# lorabreakout.net
KiCad netlist of a schematic drawn in Altium Designer
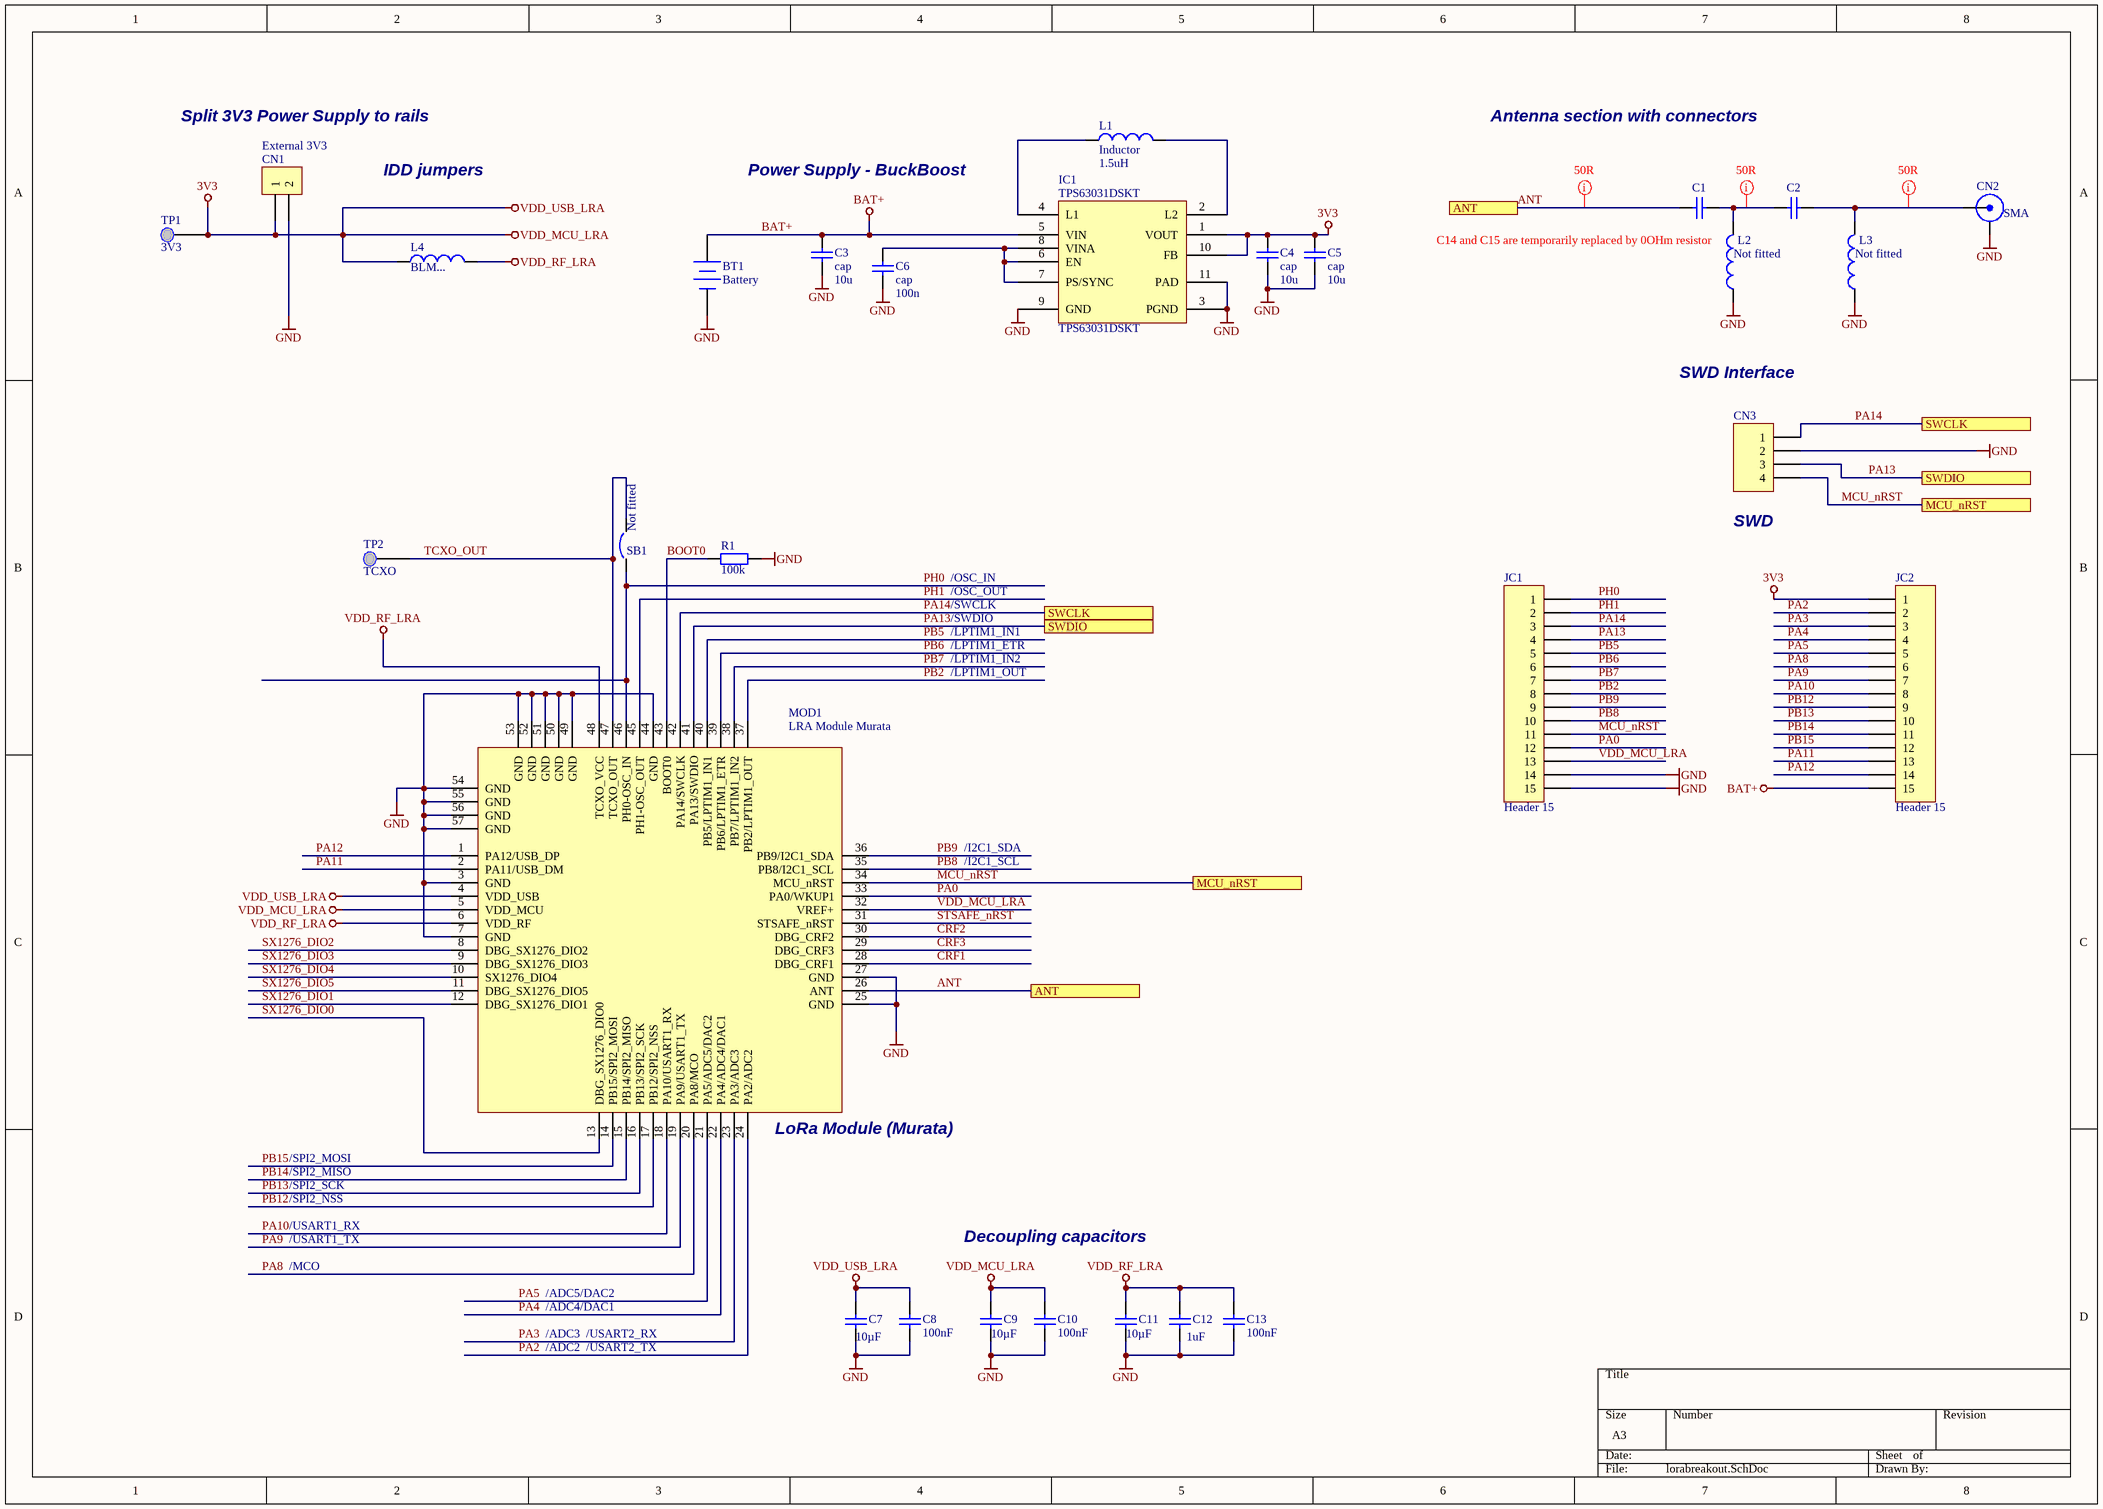
[diagram p0: lorabreakout.SchDoc]

(export (version "E")
  (design (tool "Eeschema 10.0.6"))
  (components
    (comp (ref "BT1")
      (value "Battery")
      (footprint "SIP2")
      (description "Multicell Battery")
      (fields (field (name "PUBLISHER") "Altium Limited"))
      (libsource (lib "Miscellaneous Devices") (part "Battery"))
    )
    (comp (ref "C1")
      (value "~")
      (footprint "0402")
      (description "0402")
      (libsource (lib "Capacitor_0402") (part "CAP SMD 0402 NPO 18PF 16V 5%"))
    )
    (comp (ref "C2")
      (value "~")
      (footprint "0402")
      (description "0402")
      (libsource (lib "Capacitor_0402") (part "CAP SMD 0402 NPO 18PF 16V 5%"))
    )
    (comp (ref "C3")
      (value "cap")
      (footprint "0603ok")
      (description "Capacitor")
      (fields (field (name "ALTIUM_VALUE") "10u") (field (name "PUBLISHER") "Altium Limited"))
      (libsource (lib "Miscellaneous Devices") (part "Cap"))
    )
    (comp (ref "C4")
      (value "cap")
      (footprint "0603ok")
      (description "Capacitor")
      (fields (field (name "ALTIUM_VALUE") "10u") (field (name "PUBLISHER") "Altium Limited"))
      (libsource (lib "Miscellaneous Devices") (part "Cap"))
    )
    (comp (ref "C5")
      (value "cap")
      (footprint "0603ok")
      (description "Capacitor")
      (fields (field (name "ALTIUM_VALUE") "10u") (field (name "PUBLISHER") "Altium Limited"))
      (libsource (lib "Miscellaneous Devices") (part "Cap"))
    )
    (comp (ref "C6")
      (value "cap")
      (footprint "0603ok")
      (description "Capacitor")
      (fields (field (name "ALTIUM_VALUE") "100n") (field (name "PUBLISHER") "Altium Limited"))
      (libsource (lib "Miscellaneous Devices") (part "Cap"))
    )
    (comp (ref "C7")
      (value "10µF")
      (footprint "0603C")
      (description "Capacitor SMD 0805 10000000pF X7R 10V +/-10%")
      (fields (field (name "MANUFACTURER") "Kemet") (field (name "TOLERANCE") "10%"))
      (libsource (lib "Capacitor_0805") (part "CAP_C0805C106K8RACTU"))
    )
    (comp (ref "C8")
      (value "100nF")
      (footprint "0603C")
      (description "Capacitor 100nF")
      (fields (field (name "MANUFACTURER") "YAGEO") (field (name "PROVIDED BY") "Subcon"))
      (libsource (lib "MCD16-033-STM32_LRA_Eval_Board_1") (part "CAP"))
    )
    (comp (ref "C9")
      (value "10µF")
      (footprint "0603C")
      (description "Capacitor SMD 0805 10000000pF X7R 10V +/-10%")
      (fields (field (name "MANUFACTURER") "Kemet") (field (name "TOLERANCE") "10%"))
      (libsource (lib "Capacitor_0805") (part "CAP_C0805C106K8RACTU"))
    )
    (comp (ref "C10")
      (value "100nF")
      (footprint "0603C")
      (description "Capacitor 100nF")
      (fields (field (name "MANUFACTURER") "YAGEO") (field (name "PROVIDED BY") "Subcon"))
      (libsource (lib "MCD16-033-STM32_LRA_Eval_Board_1") (part "CAP"))
    )
    (comp (ref "C11")
      (value "10µF")
      (footprint "0603C")
      (description "Capacitor SMD 0805 10000000pF X7R 10V +/-10%")
      (fields (field (name "MANUFACTURER") "Kemet") (field (name "TOLERANCE") "10%"))
      (libsource (lib "Capacitor_0805") (part "CAP_C0805C106K8RACTU"))
    )
    (comp (ref "C12")
      (value "1uF")
      (footprint "0603C")
      (description "0603  X5R 1µF")
      (fields (field (name "MANUFACTURER") "YAGEO") (field (name "PROVIDED BY") "Subcon"))
      (libsource (lib "MCD16-033-STM32_LRA_Eval_Board_1") (part "CAP SMD 0603  X5R 1µF 25V 10%"))
    )
    (comp (ref "C13")
      (value "100nF")
      (footprint "0603C")
      (description "Capacitor 100nF")
      (fields (field (name "MANUFACTURER") "YAGEO") (field (name "PROVIDED BY") "Subcon"))
      (libsource (lib "MCD16-033-STM32_LRA_Eval_Board_1") (part "CAP"))
    )
    (comp (ref "CN1")
      (value "External 3V3")
      (footprint "SIP2")
      (description "Header 2")
      (fields (field (name "MANUFACTURER") "Kontek") (field (name "PROVIDED BY") "Subcon"))
      (libsource (lib "MCD16-033-STM32_LRA_Eval_Board_1") (part "Header 2"))
    )
    (comp (ref "CN2")
      (value "SMA")
      (footprint "SMA_COMBO_B")
      (libsource (lib "SCH_Lib_Phil_ST") (part "SMA"))
    )
    (comp (ref "CN3")
      (value "Header 4")
      (footprint "SIP4")
      (description "Header, 4-Pin, Single row")
      (fields (field (name "MANUFACTURER") "Lyconn") (field (name "PROVIDED BY") "Subcon"))
      (libsource (lib "MCD16-033-STM32_LRA_Eval_Board_1") (part "Header 4"))
    )
    (comp (ref "IC1")
      (value "TPS63031DSKT")
      (footprint "QFN50P250X250X80_HS-11N")
      (libsource (lib "moja") (part "TPS63031DSKT"))
    )
    (comp (ref "JC1")
      (value "Header 15")
      (footprint "HDR1X15")
      (description "Header, 15-Pin")
      (fields (field (name "PUBLISHER") "Altium Limited"))
      (libsource (lib "") (part "Header 15_1"))
    )
    (comp (ref "JC2")
      (value "Header 15")
      (footprint "HDR1X15")
      (description "Header, 15-Pin")
      (fields (field (name "PUBLISHER") "Altium Limited"))
      (libsource (lib "Miscellaneous Connectors") (part "Header 15"))
    )
    (comp (ref "L1")
      (value "Inductor")
      (footprint "lps3015")
      (fields (field (name "ALTIUM_VALUE") "1.5uH") (field (name "PUBLISHER") "Altium Limited"))
      (libsource (lib "Miscellaneous Devices") (part "Inductor"))
    )
    (comp (ref "L2")
      (value "~")
      (footprint "0402")
      (libsource (lib "MCD16-033-STM32_LRA_Eval_Board_1") (part "BLM15HG102SN1D"))
    )
    (comp (ref "L3")
      (value "~")
      (footprint "0402")
      (libsource (lib "MCD16-033-STM32_LRA_Eval_Board_1") (part "BLM15HG102SN1D"))
    )
    (comp (ref "L4")
      (value "BLM...")
      (footprint "0603ok")
      (description "BLM15HG102SN1D")
      (fields (field (name "MANUFACTURER") "Murata Electronics"))
      (libsource (lib "MCD16-033-STM32_LRA_Eval_Board_1") (part "BLM15HG102SN1D"))
    )
    (comp (ref "MOD1")
      (value "LRA Module Murata")
      (footprint "Lora Module ES0")
      (description "LRA Module ES0")
      (fields (field (name "MANUFACTURER") "Murata") (field (name "PROVIDED BY") "Murata"))
      (libsource (lib "Integrated_Circuit") (part "LRA Module ES0"))
    )
    (comp (ref "R1")
      (value "100k")
      (footprint "0402")
      (description "2k2")
      (fields (field (name "Comment") "Res2") (field (name "PUBLISHER") "Altium Limited"))
      (libsource (lib "Miscellaneous Devices") (part "Res2"))
    )
    (comp (ref "SB1")
      (value "Circuit Breaker")
      (footprint "JP2_SMD")
      (libsource (lib "MCD16-033-STM32_LRA_Eval_Board_1") (part "Circuit Breaker"))
    )
    (comp (ref "TP1") (value "3V3") (footprint "SMD-MINITP") (libsource (lib "moja") (part "Testpoint")))
    (comp (ref "TP2") (value "TCXO") (footprint "SMD-MINITP") (libsource (lib "moja") (part "Testpoint")))
  )
  (nets
    (net (code "1") (name "/ANT") (class "Default")
      (node (ref "C1") (pin "1") (pinfunction "1_1") (pintype "passive"))
      (node (ref "MOD1") (pin "26") (pinfunction "ANT_26") (pintype "passive"))
    )
    (net (code "2") (name "/BOOT0") (class "Default")
      (node (ref "MOD1") (pin "43") (pinfunction "BOOT0_43") (pintype "passive"))
      (node (ref "R1") (pin "2") (pinfunction "2_2") (pintype "passive"))
    )
    (net (code "3") (name "/CRF1") (class "Default")
      (node (ref "MOD1") (pin "28") (pinfunction "DBG_CRF1_28") (pintype "passive"))
    )
    (net (code "4") (name "/CRF2") (class "Default")
      (node (ref "MOD1") (pin "30") (pinfunction "DBG_CRF2_30") (pintype "passive"))
    )
    (net (code "5") (name "/CRF3") (class "Default")
      (node (ref "MOD1") (pin "29") (pinfunction "DBG_CRF3_29") (pintype "passive"))
    )
    (net (code "6") (name "/MCU_nRST") (class "Default")
      (node (ref "CN3") (pin "4") (pinfunction "4_4") (pintype "passive"))
      (node (ref "JC1") (pin "11") (pinfunction "11_11") (pintype "passive"))
      (node (ref "MOD1") (pin "34") (pinfunction "MCU_nRST_34") (pintype "passive"))
    )
    (net (code "7") (name "/PA0") (class "Default")
      (node (ref "JC1") (pin "12") (pinfunction "12_12") (pintype "passive"))
      (node (ref "MOD1") (pin "33") (pinfunction "PA0/WKUP1_33") (pintype "passive"))
    )
    (net (code "8") (name "/PA2") (class "Default")
      (node (ref "JC2") (pin "2") (pinfunction "2_2") (pintype "passive"))
      (node (ref "MOD1") (pin "24") (pinfunction "PA2/ADC2_24") (pintype "passive"))
    )
    (net (code "9") (name "/PA3") (class "Default")
      (node (ref "JC2") (pin "3") (pinfunction "3_3") (pintype "passive"))
      (node (ref "MOD1") (pin "23") (pinfunction "PA3/ADC3_23") (pintype "passive"))
    )
    (net (code "10") (name "/PA4") (class "Default")
      (node (ref "JC2") (pin "4") (pinfunction "4_4") (pintype "passive"))
      (node (ref "MOD1") (pin "22") (pinfunction "PA4/ADC4/DAC1_22") (pintype "passive"))
    )
    (net (code "11") (name "/PA5") (class "Default")
      (node (ref "JC2") (pin "5") (pinfunction "5_5") (pintype "passive"))
      (node (ref "MOD1") (pin "21") (pinfunction "PA5/ADC5/DAC2_21") (pintype "passive"))
    )
    (net (code "12") (name "/PA8") (class "Default")
      (node (ref "JC2") (pin "6") (pinfunction "6_6") (pintype "passive"))
      (node (ref "MOD1") (pin "20") (pinfunction "PA8/MCO_20") (pintype "passive"))
    )
    (net (code "13") (name "/PA9") (class "Default")
      (node (ref "JC2") (pin "7") (pinfunction "7_7") (pintype "passive"))
      (node (ref "MOD1") (pin "19") (pinfunction "PA9/USART1_TX_19") (pintype "passive"))
    )
    (net (code "14") (name "/PA10") (class "Default")
      (node (ref "JC2") (pin "8") (pinfunction "8_8") (pintype "passive"))
      (node (ref "MOD1") (pin "18") (pinfunction "PA10/USART1_RX_18") (pintype "passive"))
    )
    (net (code "15") (name "/PA11") (class "Default")
      (node (ref "JC2") (pin "13") (pinfunction "13_13") (pintype "passive"))
      (node (ref "MOD1") (pin "2") (pinfunction "PA11/USB_DM_2") (pintype "passive"))
    )
    (net (code "16") (name "/PA12") (class "Default")
      (node (ref "JC2") (pin "14") (pinfunction "14_14") (pintype "passive"))
      (node (ref "MOD1") (pin "1") (pinfunction "PA12/USB_DP_1") (pintype "passive"))
    )
    (net (code "17") (name "/PA13") (class "Default")
      (node (ref "CN3") (pin "3") (pinfunction "3_3") (pintype "passive"))
      (node (ref "JC1") (pin "4") (pinfunction "4_4") (pintype "passive"))
      (node (ref "MOD1") (pin "41") (pinfunction "PA13/SWDIO_41") (pintype "passive"))
    )
    (net (code "18") (name "/PA14") (class "Default")
      (node (ref "CN3") (pin "1") (pinfunction "1_1") (pintype "passive"))
      (node (ref "JC1") (pin "3") (pinfunction "3_3") (pintype "passive"))
      (node (ref "MOD1") (pin "42") (pinfunction "PA14/SWCLK_42") (pintype "passive"))
    )
    (net (code "19") (name "/PB2") (class "Default")
      (node (ref "JC1") (pin "8") (pinfunction "8_8") (pintype "passive"))
      (node (ref "MOD1") (pin "37") (pinfunction "PB2/LPTIM1_OUT_37") (pintype "passive"))
    )
    (net (code "20") (name "/PB5") (class "Default")
      (node (ref "JC1") (pin "5") (pinfunction "5_5") (pintype "passive"))
      (node (ref "MOD1") (pin "40") (pinfunction "PB5/LPTIM1_IN1_40") (pintype "passive"))
    )
    (net (code "21") (name "/PB6") (class "Default")
      (node (ref "JC1") (pin "6") (pinfunction "6_6") (pintype "passive"))
      (node (ref "MOD1") (pin "39") (pinfunction "PB6/LPTIM1_ETR_39") (pintype "passive"))
    )
    (net (code "22") (name "/PB7") (class "Default")
      (node (ref "JC1") (pin "7") (pinfunction "7_7") (pintype "passive"))
      (node (ref "MOD1") (pin "38") (pinfunction "PB7/LPTIM1_IN2_38") (pintype "passive"))
    )
    (net (code "23") (name "/PB8") (class "Default")
      (node (ref "JC1") (pin "10") (pinfunction "10_10") (pintype "passive"))
      (node (ref "MOD1") (pin "35") (pinfunction "PB8/I2C1_SCL_35") (pintype "passive"))
    )
    (net (code "24") (name "/PB9") (class "Default")
      (node (ref "JC1") (pin "9") (pinfunction "9_9") (pintype "passive"))
      (node (ref "MOD1") (pin "36") (pinfunction "PB9/I2C1_SDA_36") (pintype "passive"))
    )
    (net (code "25") (name "/PB12") (class "Default")
      (node (ref "JC2") (pin "9") (pinfunction "9_9") (pintype "passive"))
      (node (ref "MOD1") (pin "17") (pinfunction "PB12/SPI2_NSS_17") (pintype "passive"))
    )
    (net (code "26") (name "/PB13") (class "Default")
      (node (ref "JC2") (pin "10") (pinfunction "10_10") (pintype "passive"))
      (node (ref "MOD1") (pin "16") (pinfunction "PB13/SPI2_SCK_16") (pintype "passive"))
    )
    (net (code "27") (name "/PB14") (class "Default")
      (node (ref "JC2") (pin "11") (pinfunction "11_11") (pintype "passive"))
      (node (ref "MOD1") (pin "15") (pinfunction "PB14/SPI2_MISO_15") (pintype "passive"))
    )
    (net (code "28") (name "/PB15") (class "Default")
      (node (ref "JC2") (pin "12") (pinfunction "12_12") (pintype "passive"))
      (node (ref "MOD1") (pin "14") (pinfunction "PB15/SPI2_MOSI_14") (pintype "passive"))
    )
    (net (code "29") (name "/PH0") (class "Default")
      (node (ref "JC1") (pin "1") (pinfunction "1_1") (pintype "passive"))
      (node (ref "MOD1") (pin "46") (pinfunction "PH0-OSC_IN_46") (pintype "passive"))
      (node (ref "SB1") (pin "1") (pinfunction "1_1") (pintype "passive"))
    )
    (net (code "30") (name "/PH1") (class "Default")
      (node (ref "JC1") (pin "2") (pinfunction "2_2") (pintype "passive"))
      (node (ref "MOD1") (pin "45") (pinfunction "PH1-OSC_OUT_45") (pintype "passive"))
    )
    (net (code "31") (name "/STSAFE_nRST") (class "Default")
      (node (ref "MOD1") (pin "31") (pinfunction "STSAFE_nRST_31") (pintype "passive"))
    )
    (net (code "32") (name "/SX1276_DIO0") (class "Default")
      (node (ref "MOD1") (pin "13") (pinfunction "DBG_SX1276_DIO0_13") (pintype "passive"))
    )
    (net (code "33") (name "/SX1276_DIO1") (class "Default")
      (node (ref "MOD1") (pin "12") (pinfunction "DBG_SX1276_DIO1_12") (pintype "passive"))
    )
    (net (code "34") (name "/SX1276_DIO2") (class "Default")
      (node (ref "MOD1") (pin "8") (pinfunction "DBG_SX1276_DIO2_8") (pintype "passive"))
    )
    (net (code "35") (name "/SX1276_DIO3") (class "Default")
      (node (ref "MOD1") (pin "9") (pinfunction "DBG_SX1276_DIO3_9") (pintype "passive"))
    )
    (net (code "36") (name "/SX1276_DIO4") (class "Default")
      (node (ref "MOD1") (pin "10") (pinfunction "SX1276_DIO4_10") (pintype "passive"))
    )
    (net (code "37") (name "/SX1276_DIO5") (class "Default")
      (node (ref "MOD1") (pin "11") (pinfunction "DBG_SX1276_DIO5_11") (pintype "passive"))
    )
    (net (code "38") (name "/TCXO_OUT") (class "Default")
      (node (ref "MOD1") (pin "47") (pinfunction "TCXO_OUT_47") (pintype "passive"))
      (node (ref "SB1") (pin "2") (pinfunction "2_2") (pintype "passive"))
      (node (ref "TP2") (pin "1") (pinfunction "1_1") (pintype "passive"))
    )
    (net (code "39") (name "3V3") (class "Default")
      (node (ref "C10") (pin "2") (pinfunction "2_2") (pintype "passive"))
      (node (ref "C4") (pin "2") (pinfunction "2_2") (pintype "passive"))
      (node (ref "C5") (pin "2") (pinfunction "2_2") (pintype "passive"))
      (node (ref "C7") (pin "1") (pinfunction "1_1") (pintype "passive"))
      (node (ref "C8") (pin "2") (pinfunction "2_2") (pintype "passive"))
      (node (ref "C9") (pin "1") (pinfunction "1_1") (pintype "passive"))
      (node (ref "CN1") (pin "1") (pinfunction "1_1") (pintype "passive"))
      (node (ref "IC1") (pin "1") (pinfunction "VOUT_1") (pintype "passive"))
      (node (ref "IC1") (pin "10") (pinfunction "FB_10") (pintype "passive"))
      (node (ref "JC1") (pin "13") (pinfunction "13_13") (pintype "passive"))
      (node (ref "JC2") (pin "1") (pinfunction "1_1") (pintype "passive"))
      (node (ref "L4") (pin "1") (pinfunction "1_1") (pintype "passive"))
      (node (ref "MOD1") (pin "32") (pinfunction "VREF+_32") (pintype "passive"))
      (node (ref "MOD1") (pin "4") (pinfunction "VDD_USB_4") (pintype "passive"))
      (node (ref "MOD1") (pin "5") (pinfunction "VDD_MCU_5") (pintype "passive"))
      (node (ref "TP1") (pin "1") (pinfunction "1_1") (pintype "passive"))
    )
    (net (code "40") (name "BAT+") (class "Default")
      (node (ref "BT1") (pin "1") (pinfunction "+_1") (pintype "passive"))
      (node (ref "C3") (pin "2") (pinfunction "2_2") (pintype "passive"))
      (node (ref "IC1") (pin "5") (pinfunction "VIN_5") (pintype "passive"))
      (node (ref "JC2") (pin "15") (pinfunction "15_15") (pintype "passive"))
    )
    (net (code "41") (name "GND") (class "Default")
      (node (ref "BT1") (pin "2") (pinfunction "-_2") (pintype "passive"))
      (node (ref "C10") (pin "1") (pinfunction "1_1") (pintype "passive"))
      (node (ref "C11") (pin "2") (pinfunction "2_2") (pintype "passive"))
      (node (ref "C12") (pin "1") (pinfunction "1_1") (pintype "passive"))
      (node (ref "C13") (pin "1") (pinfunction "1_1") (pintype "passive"))
      (node (ref "C3") (pin "1") (pinfunction "1_1") (pintype "passive"))
      (node (ref "C4") (pin "1") (pinfunction "1_1") (pintype "passive"))
      (node (ref "C5") (pin "1") (pinfunction "1_1") (pintype "passive"))
      (node (ref "C6") (pin "1") (pinfunction "1_1") (pintype "passive"))
      (node (ref "C7") (pin "2") (pinfunction "2_2") (pintype "passive"))
      (node (ref "C8") (pin "1") (pinfunction "1_1") (pintype "passive"))
      (node (ref "C9") (pin "2") (pinfunction "2_2") (pintype "passive"))
      (node (ref "CN1") (pin "2") (pinfunction "2_2") (pintype "passive"))
      (node (ref "CN2") (pin "2") (pinfunction "Y_2") (pintype "passive"))
      (node (ref "CN3") (pin "2") (pinfunction "2_2") (pintype "passive"))
      (node (ref "IC1") (pin "11") (pinfunction "PAD_11") (pintype "passive"))
      (node (ref "IC1") (pin "3") (pinfunction "PGND_3") (pintype "passive"))
      (node (ref "IC1") (pin "9") (pinfunction "GND_9") (pintype "passive"))
      (node (ref "JC1") (pin "14") (pinfunction "14_14") (pintype "passive"))
      (node (ref "JC1") (pin "15") (pinfunction "15_15") (pintype "passive"))
      (node (ref "L2") (pin "1") (pinfunction "1_1") (pintype "passive"))
      (node (ref "L3") (pin "1") (pinfunction "1_1") (pintype "passive"))
      (node (ref "MOD1") (pin "25") (pinfunction "GND_25") (pintype "passive"))
      (node (ref "MOD1") (pin "27") (pinfunction "GND_27") (pintype "passive"))
      (node (ref "MOD1") (pin "3") (pinfunction "GND_3") (pintype "passive"))
      (node (ref "MOD1") (pin "44") (pinfunction "GND_44") (pintype "passive"))
      (node (ref "MOD1") (pin "49") (pinfunction "GND_49") (pintype "passive"))
      (node (ref "MOD1") (pin "50") (pinfunction "GND_50") (pintype "passive"))
      (node (ref "MOD1") (pin "51") (pinfunction "GND_51") (pintype "passive"))
      (node (ref "MOD1") (pin "52") (pinfunction "GND_52") (pintype "passive"))
      (node (ref "MOD1") (pin "53") (pinfunction "GND_53") (pintype "passive"))
      (node (ref "MOD1") (pin "54") (pinfunction "GND_54") (pintype "passive"))
      (node (ref "MOD1") (pin "55") (pinfunction "GND_55") (pintype "passive"))
      (node (ref "MOD1") (pin "56") (pinfunction "GND_56") (pintype "passive"))
      (node (ref "MOD1") (pin "57") (pinfunction "GND_57") (pintype "passive"))
      (node (ref "MOD1") (pin "7") (pinfunction "GND_7") (pintype "passive"))
      (node (ref "R1") (pin "1") (pinfunction "1_1") (pintype "passive"))
    )
    (net (code "42") (name "Net-(C1-Pad2)") (class "Default")
      (node (ref "C1") (pin "2") (pinfunction "2_2") (pintype "passive"))
      (node (ref "C2") (pin "1") (pinfunction "1_1") (pintype "passive"))
      (node (ref "L2") (pin "2") (pinfunction "2_2") (pintype "passive"))
    )
    (net (code "43") (name "Net-(CN2-X)") (class "Default")
      (node (ref "C2") (pin "2") (pinfunction "2_2") (pintype "passive"))
      (node (ref "CN2") (pin "1") (pinfunction "X_1") (pintype "passive"))
      (node (ref "L3") (pin "2") (pinfunction "2_2") (pintype "passive"))
    )
    (net (code "44") (name "Net-(IC1-EN)") (class "Default")
      (node (ref "C6") (pin "2") (pinfunction "2_2") (pintype "passive"))
      (node (ref "IC1") (pin "6") (pinfunction "EN_6") (pintype "passive"))
      (node (ref "IC1") (pin "7") (pinfunction "PS/SYNC_7") (pintype "passive"))
      (node (ref "IC1") (pin "8") (pinfunction "VINA_8") (pintype "passive"))
    )
    (net (code "45") (name "Net-(IC1-L1)") (class "Default")
      (node (ref "IC1") (pin "4") (pinfunction "L1_4") (pintype "passive"))
      (node (ref "L1") (pin "1") (pinfunction "1_1") (pintype "passive"))
    )
    (net (code "46") (name "Net-(IC1-L2)") (class "Default")
      (node (ref "IC1") (pin "2") (pinfunction "L2_2") (pintype "passive"))
      (node (ref "L1") (pin "2") (pinfunction "2_2") (pintype "passive"))
    )
    (net (code "47") (name "VDD_RF_LRA") (class "Default")
      (node (ref "C11") (pin "1") (pinfunction "1_1") (pintype "passive"))
      (node (ref "C12") (pin "2") (pinfunction "2_2") (pintype "passive"))
      (node (ref "C13") (pin "2") (pinfunction "2_2") (pintype "passive"))
      (node (ref "L4") (pin "2") (pinfunction "2_2") (pintype "passive"))
      (node (ref "MOD1") (pin "48") (pinfunction "TCXO_VCC_48") (pintype "passive"))
      (node (ref "MOD1") (pin "6") (pinfunction "VDD_RF_6") (pintype "passive"))
    )
  )
)
